# atxmega_e5_breakout_v1.net
KiCad netlist of a schematic drawn in EAGLE
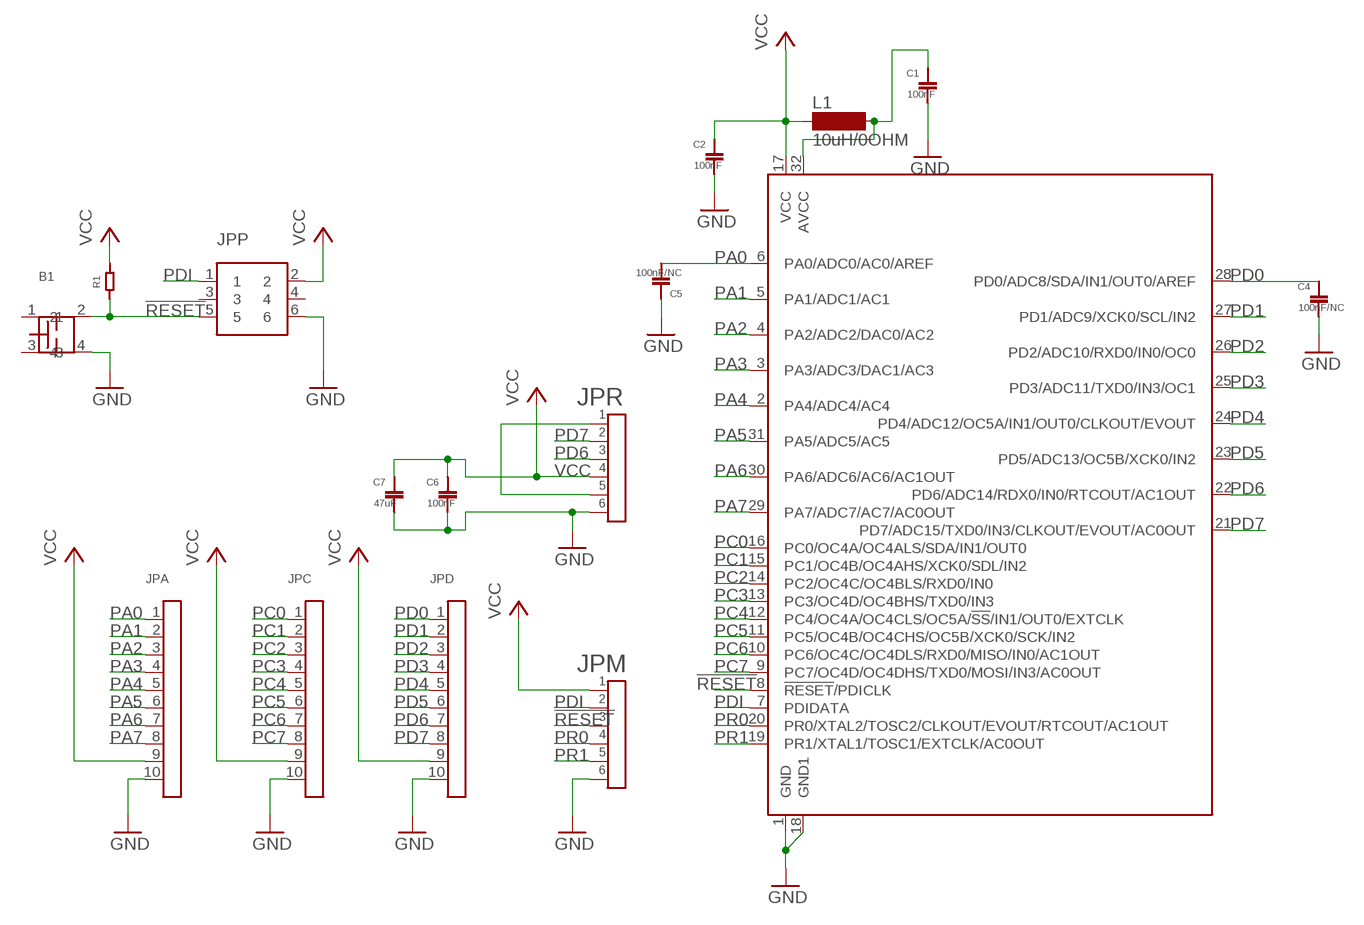
[diagram p0: schematic, sheet 1]

(export (version "E")
  (design (tool "Eeschema 10.0.6"))
  (components
    (comp (ref "B1")
      (value "BUTTON_ALPS_5.2MM_SMD")
      (footprint "eagle-import:BUTTON_ALPS_SMD_5.2MM_SKQG")
      (libsource (lib "eagle-import") (part "BUTTON_ALPS_5.2MM_SMD"))
    )
    (comp (ref "C1")
      (value "100nF")
      (footprint "eagle-import:0603")
      (libsource (lib "eagle-import") (part "CAPACITOR0603"))
    )
    (comp (ref "C2")
      (value "100nF")
      (footprint "eagle-import:0603")
      (libsource (lib "eagle-import") (part "CAPACITOR0603"))
    )
    (comp (ref "C4")
      (value "100nF/NC")
      (footprint "eagle-import:0603")
      (libsource (lib "eagle-import") (part "CAPACITOR0603"))
    )
    (comp (ref "C5")
      (value "100nF/NC")
      (footprint "eagle-import:0603")
      (libsource (lib "eagle-import") (part "CAPACITOR0603"))
    )
    (comp (ref "C6")
      (value "100nF")
      (footprint "eagle-import:0603")
      (libsource (lib "eagle-import") (part "CAPACITOR0603"))
    )
    (comp (ref "C7")
      (value "47uF")
      (footprint "eagle-import:1206")
      (libsource (lib "eagle-import") (part "CAPACITOR1206"))
    )
    (comp (ref "JPA")
      (value "PIN1X10PTH_S")
      (footprint "eagle-import:PIN_1X10_S")
      (libsource (lib "eagle-import") (part "PIN1X10PTH_S"))
    )
    (comp (ref "JPC")
      (value "PIN1X10PTH_S")
      (footprint "eagle-import:PIN_1X10_S")
      (libsource (lib "eagle-import") (part "PIN1X10PTH_S"))
    )
    (comp (ref "JPD")
      (value "PIN1X10PTH_S")
      (footprint "eagle-import:PIN_1X10_S")
      (libsource (lib "eagle-import") (part "PIN1X10PTH_S"))
    )
    (comp (ref "JPM")
      (value "PIN1X6PTH_SMALL")
      (footprint "eagle-import:PIN_1X6_S")
      (libsource (lib "eagle-import") (part "PIN1X6PTH_SMALL"))
    )
    (comp (ref "JPP")
      (value "PIN2X3ALT_S")
      (footprint "eagle-import:PIN_2X3_ALT_S")
      (libsource (lib "eagle-import") (part "PIN2X3ALT_S"))
    )
    (comp (ref "JPR")
      (value "PIN1X6PTH_SMALL")
      (footprint "eagle-import:PIN_1X6_S")
      (libsource (lib "eagle-import") (part "PIN1X6PTH_SMALL"))
    )
    (comp (ref "L1")
      (value "10uH/0OHM")
      (footprint "eagle-import:SM-1206")
      (libsource (lib "eagle-import") (part "SM-1206"))
    )
    (comp (ref "R1")
      (value "RESISTOR0603")
      (footprint "eagle-import:0603")
      (libsource (lib "eagle-import") (part "RESISTOR0603"))
    )
    (comp (ref "U1")
      (value "ATXMEGAE5AU")
      (footprint "eagle-import:TQFP32")
      (libsource (lib "eagle-import") (part "ATXMEGAE5AU"))
    )
  )
  (nets
    (net (code "1") (name "/PA0") (class "Default")
      (node (ref "C5") (pin "1") (pinfunction "2_1") (pintype "passive"))
      (node (ref "JPA") (pin "1") (pinfunction "P$1_1") (pintype "bidirectional"))
      (node (ref "U1") (pin "6") (pinfunction "PA0/ADC0/AC0/AREF_6") (pintype "bidirectional"))
    )
    (net (code "2") (name "/PA1") (class "Default")
      (node (ref "JPA") (pin "2") (pinfunction "P$2_2") (pintype "bidirectional"))
      (node (ref "U1") (pin "5") (pinfunction "PA1/ADC1/AC1_5") (pintype "bidirectional"))
    )
    (net (code "3") (name "/PA2") (class "Default")
      (node (ref "JPA") (pin "3") (pinfunction "P$3_3") (pintype "bidirectional"))
      (node (ref "U1") (pin "4") (pinfunction "PA2/ADC2/DAC0/AC2_4") (pintype "bidirectional"))
    )
    (net (code "4") (name "/PA3") (class "Default")
      (node (ref "JPA") (pin "4") (pinfunction "P$4_4") (pintype "bidirectional"))
      (node (ref "U1") (pin "3") (pinfunction "PA3/ADC3/DAC1/AC3_3") (pintype "bidirectional"))
    )
    (net (code "5") (name "/PA4") (class "Default")
      (node (ref "JPA") (pin "5") (pinfunction "P$5_5") (pintype "bidirectional"))
      (node (ref "U1") (pin "2") (pinfunction "PA4/ADC4/AC4_2") (pintype "bidirectional"))
    )
    (net (code "6") (name "/PA5") (class "Default")
      (node (ref "JPA") (pin "6") (pinfunction "P$6_6") (pintype "bidirectional"))
      (node (ref "U1") (pin "31") (pinfunction "PA5/ADC5/AC5_31") (pintype "bidirectional"))
    )
    (net (code "7") (name "/PA6") (class "Default")
      (node (ref "JPA") (pin "7") (pinfunction "P$7_7") (pintype "bidirectional"))
      (node (ref "U1") (pin "30") (pinfunction "PA6/ADC6/AC6/AC1OUT_30") (pintype "bidirectional"))
    )
    (net (code "8") (name "/PA7") (class "Default")
      (node (ref "JPA") (pin "8") (pinfunction "P$8_8") (pintype "bidirectional"))
      (node (ref "U1") (pin "29") (pinfunction "PA7/ADC7/AC7/AC0OUT_29") (pintype "bidirectional"))
    )
    (net (code "9") (name "/PC0") (class "Default")
      (node (ref "JPC") (pin "1") (pinfunction "P$1_1") (pintype "bidirectional"))
      (node (ref "U1") (pin "16") (pinfunction "PC0/OC4A/OC4ALS/SDA/IN1/OUT0_16") (pintype "bidirectional"))
    )
    (net (code "10") (name "/PC1") (class "Default")
      (node (ref "JPC") (pin "2") (pinfunction "P$2_2") (pintype "bidirectional"))
      (node (ref "U1") (pin "15") (pinfunction "PC1/OC4B/OC4AHS/XCK0/SDL/IN2_15") (pintype "bidirectional"))
    )
    (net (code "11") (name "/PC2") (class "Default")
      (node (ref "JPC") (pin "3") (pinfunction "P$3_3") (pintype "bidirectional"))
      (node (ref "U1") (pin "14") (pinfunction "PC2/OC4C/OC4BLS/RXD0/IN0_14") (pintype "bidirectional"))
    )
    (net (code "12") (name "/PC3") (class "Default")
      (node (ref "JPC") (pin "4") (pinfunction "P$4_4") (pintype "bidirectional"))
      (node (ref "U1") (pin "13") (pinfunction "PC3/OC4D/OC4BHS/TXD0/IN3_13") (pintype "bidirectional"))
    )
    (net (code "13") (name "/PC4") (class "Default")
      (node (ref "JPC") (pin "5") (pinfunction "P$5_5") (pintype "bidirectional"))
      (node (ref "U1") (pin "12") (pinfunction "PC4/OC4A/OC4CLS/OC5A/~{SS}/IN1/OUT0/EXTCLK_12") (pintype "bidirectional"))
    )
    (net (code "14") (name "/PC5") (class "Default")
      (node (ref "JPC") (pin "6") (pinfunction "P$6_6") (pintype "bidirectional"))
      (node (ref "U1") (pin "11") (pinfunction "PC5/OC4B/OC4CHS/OC5B/XCK0/SCK/IN2_11") (pintype "bidirectional"))
    )
    (net (code "15") (name "/PC6") (class "Default")
      (node (ref "JPC") (pin "7") (pinfunction "P$7_7") (pintype "bidirectional"))
      (node (ref "U1") (pin "10") (pinfunction "PC6/OC4C/OC4DLS/RXD0/MISO/IN0/AC1OUT_10") (pintype "bidirectional"))
    )
    (net (code "16") (name "/PC7") (class "Default")
      (node (ref "JPC") (pin "8") (pinfunction "P$8_8") (pintype "bidirectional"))
      (node (ref "U1") (pin "9") (pinfunction "PC7/OC4D/OC4DHS/TXD0/MOSI/IN3/AC0OUT_9") (pintype "bidirectional"))
    )
    (net (code "17") (name "/PD0") (class "Default")
      (node (ref "C4") (pin "2") (pinfunction "1_2") (pintype "passive"))
      (node (ref "JPD") (pin "1") (pinfunction "P$1_1") (pintype "bidirectional"))
      (node (ref "U1") (pin "28") (pinfunction "PD0/ADC8/SDA/IN1/OUT0/AREF_28") (pintype "bidirectional"))
    )
    (net (code "18") (name "/PD1") (class "Default")
      (node (ref "JPD") (pin "2") (pinfunction "P$2_2") (pintype "bidirectional"))
      (node (ref "U1") (pin "27") (pinfunction "PD1/ADC9/XCK0/SCL/IN2_27") (pintype "bidirectional"))
    )
    (net (code "19") (name "/PD2") (class "Default")
      (node (ref "JPD") (pin "3") (pinfunction "P$3_3") (pintype "bidirectional"))
      (node (ref "U1") (pin "26") (pinfunction "PD2/ADC10/RXD0/IN0/OC0_26") (pintype "bidirectional"))
    )
    (net (code "20") (name "/PD3") (class "Default")
      (node (ref "JPD") (pin "4") (pinfunction "P$4_4") (pintype "bidirectional"))
      (node (ref "U1") (pin "25") (pinfunction "PD3/ADC11/TXD0/IN3/OC1_25") (pintype "bidirectional"))
    )
    (net (code "21") (name "/PD4") (class "Default")
      (node (ref "JPD") (pin "5") (pinfunction "P$5_5") (pintype "bidirectional"))
      (node (ref "U1") (pin "24") (pinfunction "PD4/ADC12/OC5A/IN1/OUT0/CLKOUT/EVOUT_24") (pintype "bidirectional"))
    )
    (net (code "22") (name "/PD5") (class "Default")
      (node (ref "JPD") (pin "6") (pinfunction "P$6_6") (pintype "bidirectional"))
      (node (ref "U1") (pin "23") (pinfunction "PD5/ADC13/OC5B/XCK0/IN2_23") (pintype "bidirectional"))
    )
    (net (code "23") (name "/PD6") (class "Default")
      (node (ref "JPD") (pin "7") (pinfunction "P$7_7") (pintype "bidirectional"))
      (node (ref "JPR") (pin "3") (pinfunction "3_3") (pintype "bidirectional"))
      (node (ref "U1") (pin "22") (pinfunction "PD6/ADC14/RDX0/IN0/RTCOUT/AC1OUT_22") (pintype "bidirectional"))
    )
    (net (code "24") (name "/PD7") (class "Default")
      (node (ref "JPD") (pin "8") (pinfunction "P$8_8") (pintype "bidirectional"))
      (node (ref "JPR") (pin "2") (pinfunction "2_2") (pintype "bidirectional"))
      (node (ref "U1") (pin "21") (pinfunction "PD7/ADC15/TXD0/IN3/CLKOUT/EVOUT/AC0OUT_21") (pintype "bidirectional"))
    )
    (net (code "25") (name "/PDI") (class "Default")
      (node (ref "JPM") (pin "2") (pinfunction "2_2") (pintype "bidirectional"))
      (node (ref "JPP") (pin "1") (pinfunction "1_1") (pintype "bidirectional"))
      (node (ref "U1") (pin "7") (pinfunction "PDIDATA_7") (pintype "bidirectional"))
    )
    (net (code "26") (name "/PR0") (class "Default")
      (node (ref "JPM") (pin "4") (pinfunction "4_4") (pintype "bidirectional"))
      (node (ref "U1") (pin "20") (pinfunction "PR0/XTAL2/TOSC2/CLKOUT/EVOUT/RTCOUT/AC1OUT_20") (pintype "bidirectional"))
    )
    (net (code "27") (name "/PR1") (class "Default")
      (node (ref "JPM") (pin "5") (pinfunction "5_5") (pintype "bidirectional"))
      (node (ref "U1") (pin "19") (pinfunction "PR1/XTAL1/TOSC1/EXTCLK/AC0OUT_19") (pintype "bidirectional"))
    )
    (net (code "28") (name "/~{RESET}") (class "Default")
      (node (ref "B1") (pin "2") (pinfunction "2_2") (pintype "bidirectional"))
      (node (ref "JPM") (pin "3") (pinfunction "3_3") (pintype "bidirectional"))
      (node (ref "JPP") (pin "5") (pinfunction "5_5") (pintype "bidirectional"))
      (node (ref "R1") (pin "1") (pinfunction "1_1") (pintype "passive"))
      (node (ref "U1") (pin "8") (pinfunction "~{RESET}/PDICLK_8") (pintype "bidirectional"))
    )
    (net (code "29") (name "GND") (class "Default")
      (node (ref "B1") (pin "4") (pinfunction "4_4") (pintype "bidirectional"))
      (node (ref "C1") (pin "1") (pinfunction "2_1") (pintype "passive"))
      (node (ref "C2") (pin "1") (pinfunction "2_1") (pintype "passive"))
      (node (ref "C4") (pin "1") (pinfunction "2_1") (pintype "passive"))
      (node (ref "C5") (pin "2") (pinfunction "1_2") (pintype "passive"))
      (node (ref "C6") (pin "1") (pinfunction "2_1") (pintype "passive"))
      (node (ref "C7") (pin "2") (pinfunction "2_2") (pintype "passive"))
      (node (ref "JPA") (pin "10") (pinfunction "P$10_10") (pintype "bidirectional"))
      (node (ref "JPC") (pin "10") (pinfunction "P$10_10") (pintype "bidirectional"))
      (node (ref "JPD") (pin "10") (pinfunction "P$10_10") (pintype "bidirectional"))
      (node (ref "JPM") (pin "6") (pinfunction "6_6") (pintype "bidirectional"))
      (node (ref "JPP") (pin "6") (pinfunction "6_6") (pintype "bidirectional"))
      (node (ref "JPR") (pin "6") (pinfunction "6_6") (pintype "bidirectional"))
      (node (ref "U1") (pin "1") (pinfunction "GND_1") (pintype "bidirectional"))
      (node (ref "U1") (pin "18") (pinfunction "GND1_18") (pintype "bidirectional"))
    )
    (net (code "30") (name "Net-(C1-1)") (class "Default")
      (node (ref "C1") (pin "2") (pinfunction "1_2") (pintype "passive"))
      (node (ref "L1") (pin "2") (pinfunction "2_2") (pintype "passive"))
      (node (ref "U1") (pin "32") (pinfunction "AVCC_32") (pintype "bidirectional"))
    )
    (net (code "31") (name "Net-(JPR-Pad1)") (class "Default")
      (node (ref "JPR") (pin "1") (pinfunction "1_1") (pintype "bidirectional"))
      (node (ref "JPR") (pin "5") (pinfunction "5_5") (pintype "bidirectional"))
    )
    (net (code "32") (name "VCC") (class "Default")
      (node (ref "C2") (pin "2") (pinfunction "1_2") (pintype "passive"))
      (node (ref "C6") (pin "2") (pinfunction "1_2") (pintype "passive"))
      (node (ref "C7") (pin "1") (pinfunction "1_1") (pintype "passive"))
      (node (ref "JPA") (pin "9") (pinfunction "P$9_9") (pintype "bidirectional"))
      (node (ref "JPC") (pin "9") (pinfunction "P$9_9") (pintype "bidirectional"))
      (node (ref "JPD") (pin "9") (pinfunction "P$9_9") (pintype "bidirectional"))
      (node (ref "JPM") (pin "1") (pinfunction "1_1") (pintype "bidirectional"))
      (node (ref "JPP") (pin "2") (pinfunction "2_2") (pintype "bidirectional"))
      (node (ref "JPR") (pin "4") (pinfunction "4_4") (pintype "bidirectional"))
      (node (ref "L1") (pin "1") (pinfunction "1_1") (pintype "passive"))
      (node (ref "R1") (pin "2") (pinfunction "2_2") (pintype "passive"))
      (node (ref "U1") (pin "17") (pinfunction "VCC_17") (pintype "bidirectional"))
    )
    (net (code "33") (name "unconnected-(B1-Pad1)") (class "Default")
      (node (ref "B1") (pin "1") (pinfunction "1_1") (pintype "bidirectional"))
    )
    (net (code "34") (name "unconnected-(B1-Pad3)") (class "Default")
      (node (ref "B1") (pin "3") (pinfunction "3_3") (pintype "bidirectional"))
    )
    (net (code "35") (name "unconnected-(JPP-Pad3)") (class "Default")
      (node (ref "JPP") (pin "3") (pinfunction "3_3") (pintype "bidirectional"))
    )
    (net (code "36") (name "unconnected-(JPP-Pad4)") (class "Default")
      (node (ref "JPP") (pin "4") (pinfunction "4_4") (pintype "bidirectional"))
    )
  )
)
